# p2cgb-001.net
KiCad netlist of a schematic drawn in EAGLE
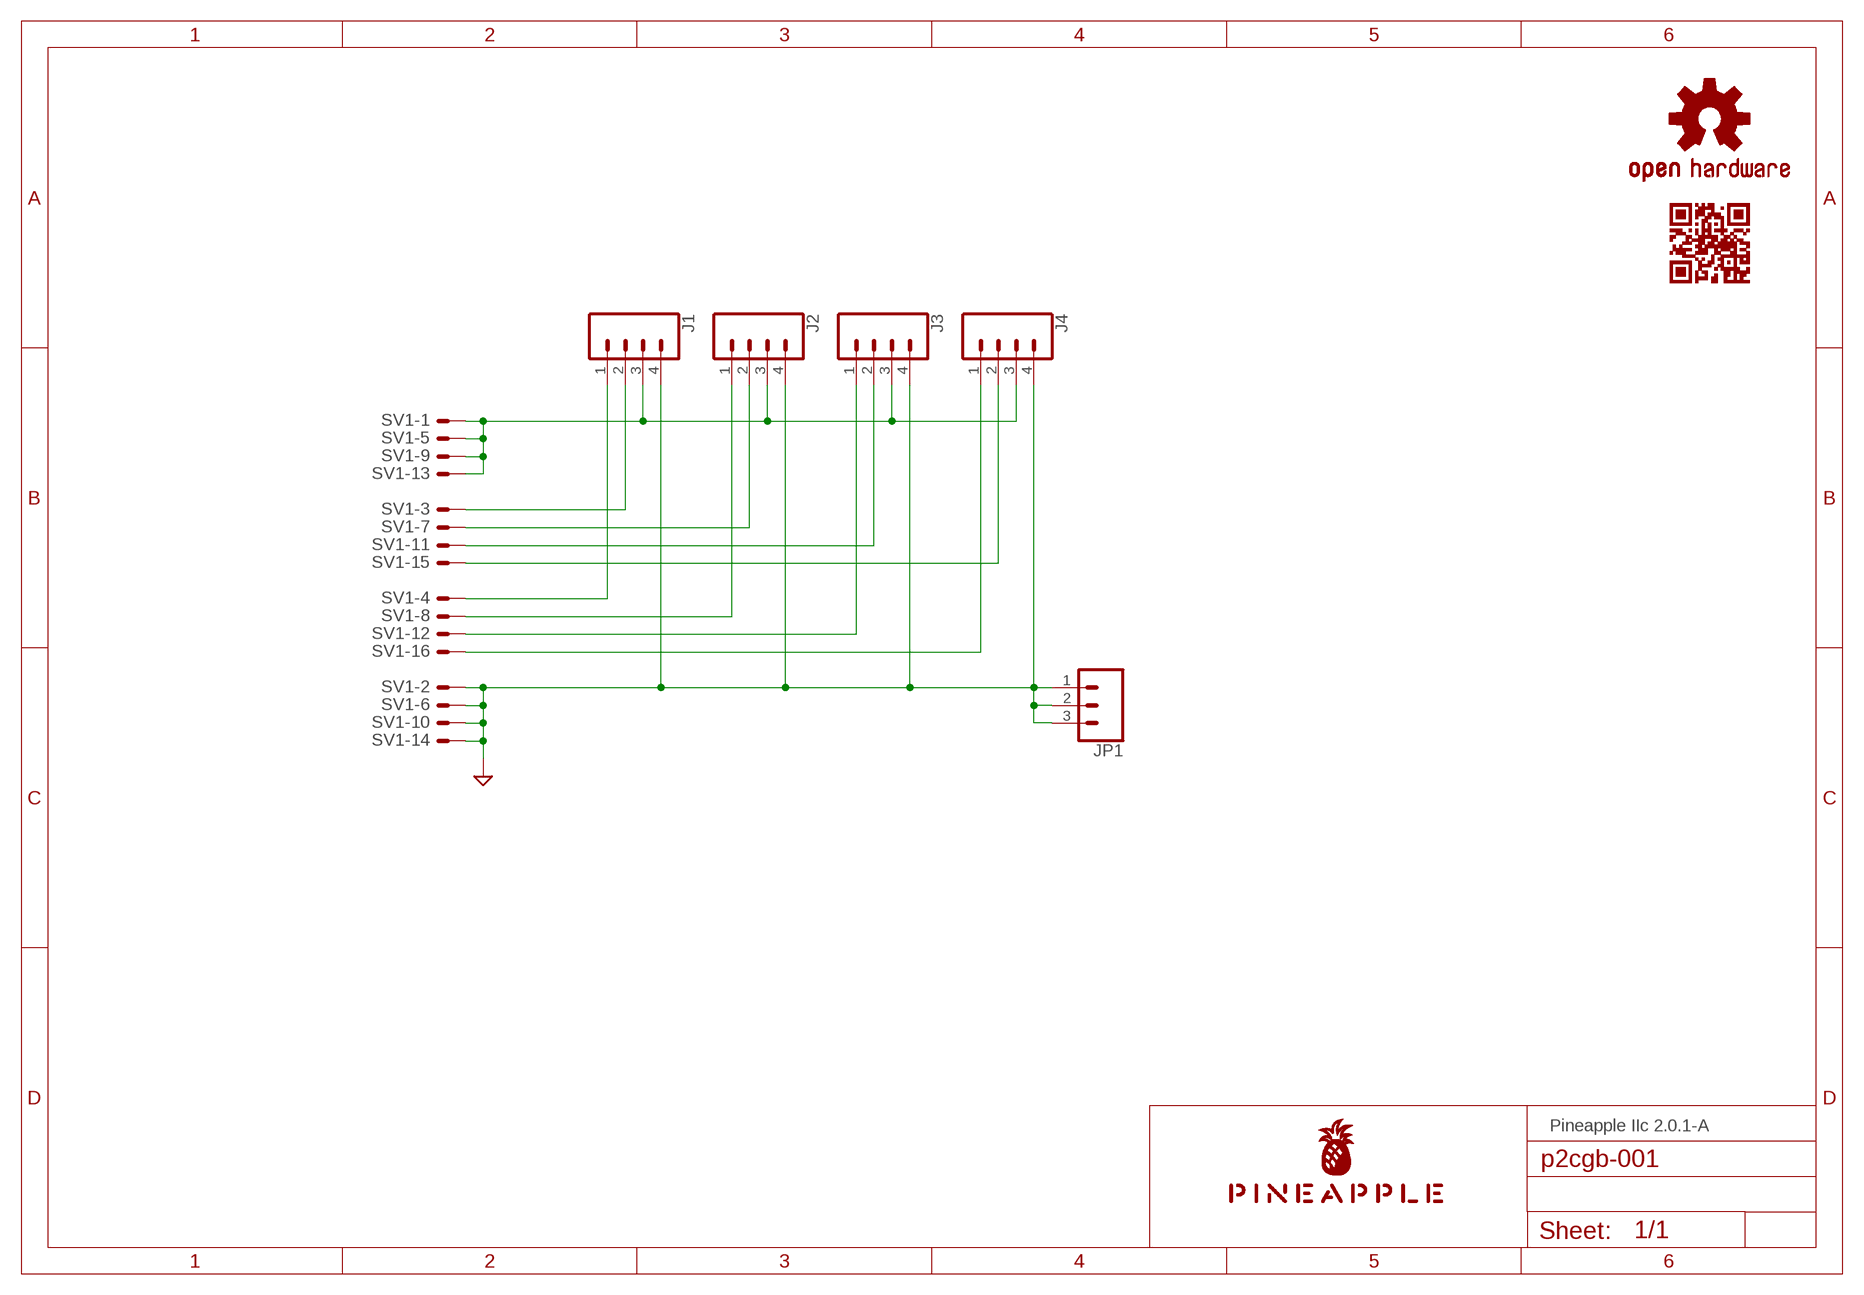
[diagram p0: schematic, sheet 1]

(export (version "E")
  (design (tool "Eeschema 10.0.6"))
  (components
    (comp (ref "J1")
      (value "CONN_04JST-PTH")
      (footprint "eagle-import:JST-4-PTH")
      (libsource (lib "eagle-import") (part "CONN_04JST-PTH"))
    )
    (comp (ref "J2")
      (value "CONN_04JST-PTH")
      (footprint "eagle-import:JST-4-PTH")
      (libsource (lib "eagle-import") (part "CONN_04JST-PTH"))
    )
    (comp (ref "J3")
      (value "CONN_04JST-PTH")
      (footprint "eagle-import:JST-4-PTH")
      (libsource (lib "eagle-import") (part "CONN_04JST-PTH"))
    )
    (comp (ref "J4")
      (value "CONN_04JST-PTH")
      (footprint "eagle-import:JST-4-PTH")
      (libsource (lib "eagle-import") (part "CONN_04JST-PTH"))
    )
    (comp (ref "JP1")
      (value "CONN_03")
      (footprint "eagle-import:1X03")
      (libsource (lib "eagle-import") (part "CONN_03"))
    )
    (comp (ref "LOGO1")
      (value "OSHW-LOGOS-COPPER")
      (footprint "eagle-import:OSHW-LOGO-S_COPPER")
      (libsource (lib "eagle-import") (part "OSHW-LOGOS-COPPER"))
    )
    (comp (ref "SV1")
      (value "ML16LE")
      (footprint "eagle-import:ML16L")
      (libsource (lib "eagle-import") (part "ML16LE"))
    )
    (comp (ref "U$1")
      (value "PINEAPPLE450_SILK")
      (footprint "eagle-import:PINEAPPLE450_SILK")
      (libsource (lib "eagle-import") (part "PINEAPPLE450_SILK"))
    )
    (comp (ref "U$4")
      (value "CARDQRCODE450_SILK")
      (footprint "eagle-import:CARDQRCODE450_SILK")
      (libsource (lib "eagle-import") (part "CARDQRCODE450_SILK"))
    )
  )
  (nets
    (net (code "1") (name "GND") (class "Default")
      (node (ref "J1") (pin "4") (pinfunction "4_4") (pintype "passive"))
      (node (ref "J2") (pin "4") (pinfunction "4_4") (pintype "passive"))
      (node (ref "J3") (pin "4") (pinfunction "4_4") (pintype "passive"))
      (node (ref "J4") (pin "4") (pinfunction "4_4") (pintype "passive"))
      (node (ref "JP1") (pin "1") (pinfunction "1_1") (pintype "passive"))
      (node (ref "JP1") (pin "2") (pinfunction "2_2") (pintype "passive"))
      (node (ref "JP1") (pin "3") (pinfunction "3_3") (pintype "passive"))
      (node (ref "SV1") (pin "10") (pinfunction "S_10") (pintype "passive"))
      (node (ref "SV1") (pin "14") (pinfunction "S_14") (pintype "passive"))
      (node (ref "SV1") (pin "2") (pinfunction "S_2") (pintype "passive"))
      (node (ref "SV1") (pin "6") (pinfunction "S_6") (pintype "passive"))
    )
    (net (code "2") (name "Net-(SV1A-S)") (class "Default")
      (node (ref "J1") (pin "3") (pinfunction "3_3") (pintype "passive"))
      (node (ref "J2") (pin "3") (pinfunction "3_3") (pintype "passive"))
      (node (ref "J3") (pin "3") (pinfunction "3_3") (pintype "passive"))
      (node (ref "J4") (pin "3") (pinfunction "3_3") (pintype "passive"))
      (node (ref "SV1") (pin "1") (pinfunction "S_1") (pintype "passive"))
      (node (ref "SV1") (pin "13") (pinfunction "S_13") (pintype "passive"))
      (node (ref "SV1") (pin "5") (pinfunction "S_5") (pintype "passive"))
      (node (ref "SV1") (pin "9") (pinfunction "S_9") (pintype "passive"))
    )
    (net (code "3") (name "Net-(SV1C-S)") (class "Default")
      (node (ref "J3") (pin "2") (pinfunction "2_2") (pintype "passive"))
      (node (ref "SV1") (pin "11") (pinfunction "S_11") (pintype "passive"))
    )
    (net (code "4") (name "Net-(SV1D-S)") (class "Default")
      (node (ref "J3") (pin "1") (pinfunction "1_1") (pintype "passive"))
      (node (ref "SV1") (pin "12") (pinfunction "S_12") (pintype "passive"))
    )
    (net (code "5") (name "Net-(SV1G-S)") (class "Default")
      (node (ref "J4") (pin "2") (pinfunction "2_2") (pintype "passive"))
      (node (ref "SV1") (pin "15") (pinfunction "S_15") (pintype "passive"))
    )
    (net (code "6") (name "Net-(SV1H-S)") (class "Default")
      (node (ref "J4") (pin "1") (pinfunction "1_1") (pintype "passive"))
      (node (ref "SV1") (pin "16") (pinfunction "S_16") (pintype "passive"))
    )
    (net (code "7") (name "Net-(SV1J-S)") (class "Default")
      (node (ref "J1") (pin "2") (pinfunction "2_2") (pintype "passive"))
      (node (ref "SV1") (pin "3") (pinfunction "S_3") (pintype "passive"))
    )
    (net (code "8") (name "Net-(SV1K-S)") (class "Default")
      (node (ref "J1") (pin "1") (pinfunction "1_1") (pintype "passive"))
      (node (ref "SV1") (pin "4") (pinfunction "S_4") (pintype "passive"))
    )
    (net (code "9") (name "Net-(SV1N-S)") (class "Default")
      (node (ref "J2") (pin "2") (pinfunction "2_2") (pintype "passive"))
      (node (ref "SV1") (pin "7") (pinfunction "S_7") (pintype "passive"))
    )
    (net (code "10") (name "Net-(SV1O-S)") (class "Default")
      (node (ref "J2") (pin "1") (pinfunction "1_1") (pintype "passive"))
      (node (ref "SV1") (pin "8") (pinfunction "S_8") (pintype "passive"))
    )
  )
)
